# MCU.net
KiCad netlist of a schematic drawn in Altium Designer
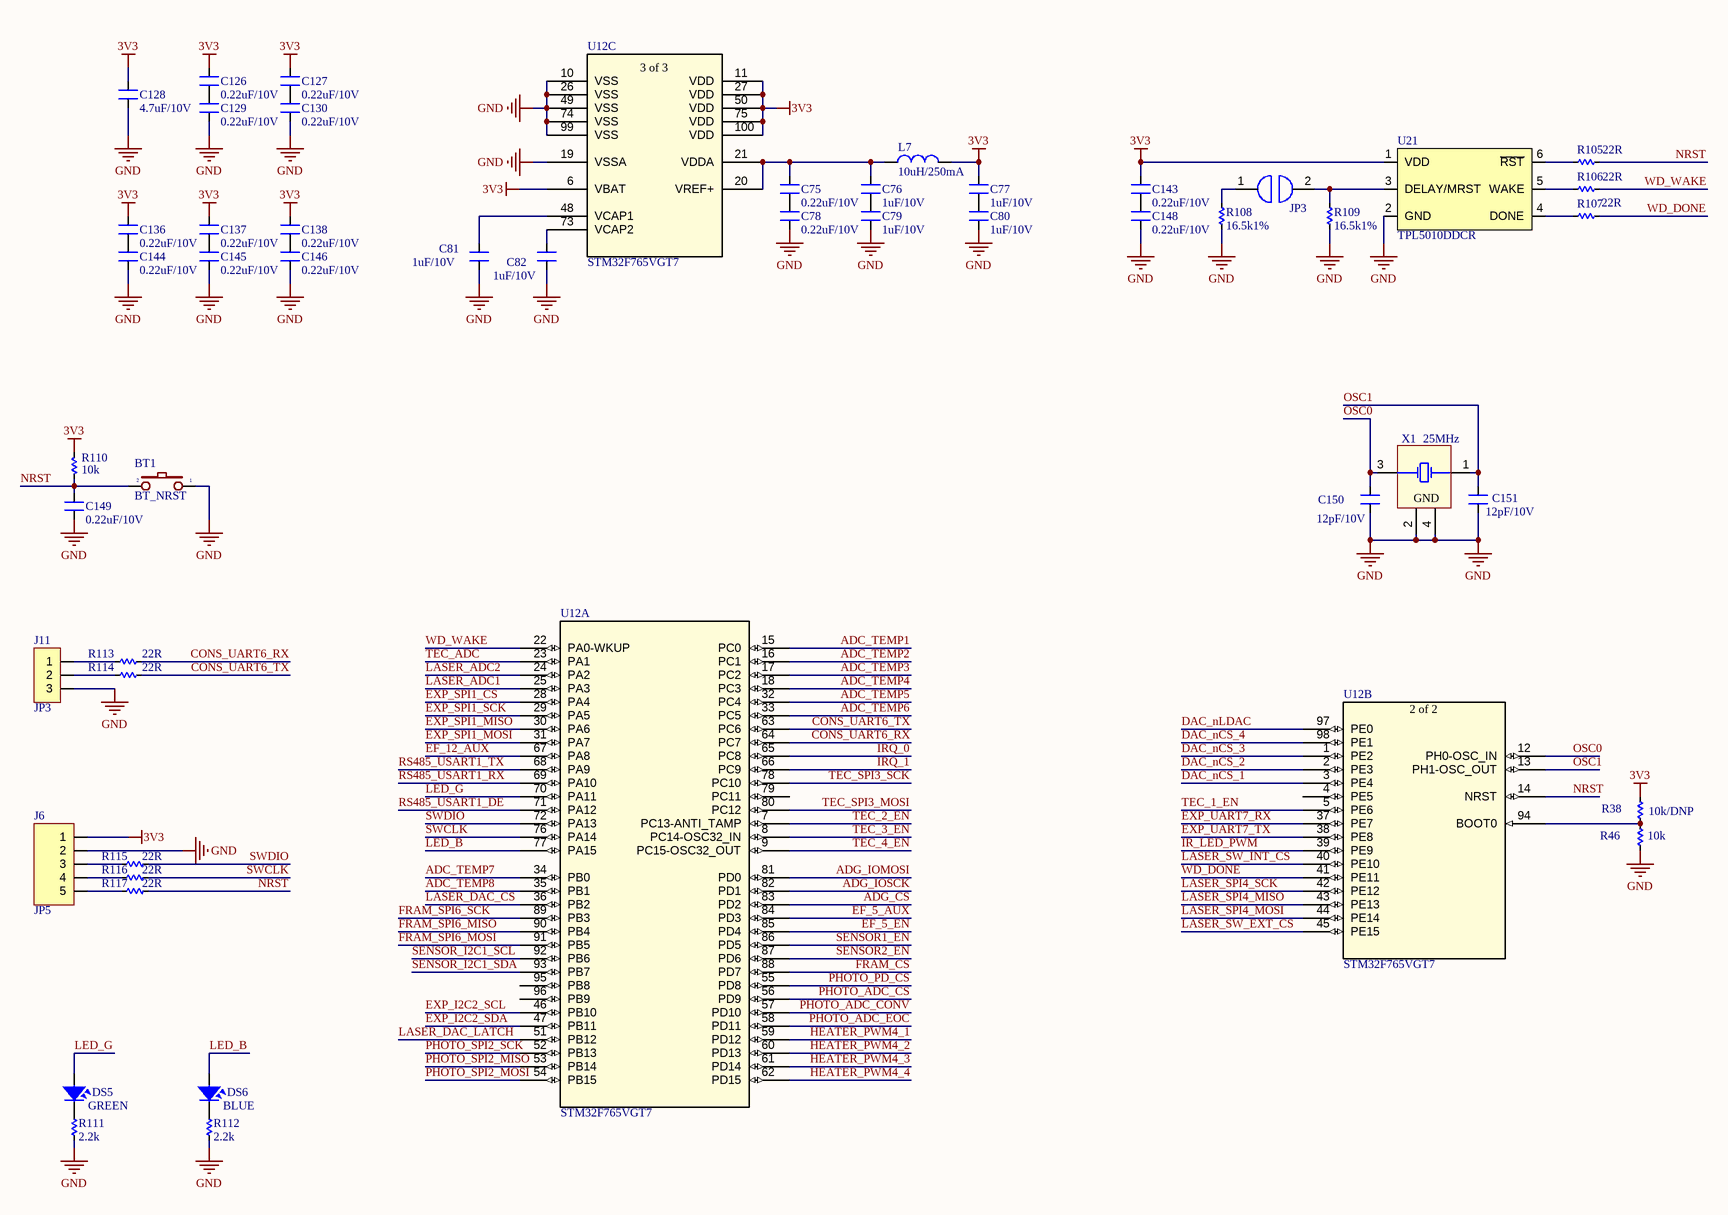
[diagram p0: MCU.SchDoc]

(export (version "E")
  (design (tool "Eeschema 10.0.6"))
  (components
    (comp (ref "BT1")
      (value "BT_NRST")
      (footprint "SW1-SMD")
      (description "Switch button 2 pin")
      (libsource (lib "EXP_HW_V3") (part "SW2"))
    )
    (comp (ref "C75")
      (value "0.22uF/10V")
      (footprint "CAP_C_1608X80")
      (libsource (lib "EXP_HW_V3") (part "Capacitors"))
    )
    (comp (ref "C76")
      (value "1uF/10V")
      (footprint "CAP_C_1608X80")
      (libsource (lib "EXP_HW_V3") (part "Capacitors"))
    )
    (comp (ref "C77")
      (value "1uF/10V")
      (footprint "CAP_C_1608X80")
      (libsource (lib "EXP_HW_V3") (part "Capacitors"))
    )
    (comp (ref "C78")
      (value "0.22uF/10V")
      (footprint "CAP_C_1608X80")
      (libsource (lib "EXP_HW_V3") (part "Capacitors"))
    )
    (comp (ref "C79")
      (value "1uF/10V")
      (footprint "CAP_C_1608X80")
      (libsource (lib "EXP_HW_V3") (part "Capacitors"))
    )
    (comp (ref "C80")
      (value "1uF/10V")
      (footprint "CAP_C_1608X80")
      (libsource (lib "EXP_HW_V3") (part "Capacitors"))
    )
    (comp (ref "C81")
      (value "1uF/10V")
      (footprint "CAP_C_1608X80")
      (libsource (lib "EXP_HW_V3") (part "Capacitors"))
    )
    (comp (ref "C82")
      (value "1uF/10V")
      (footprint "CAP_C_1608X80")
      (libsource (lib "EXP_HW_V3") (part "Capacitors"))
    )
    (comp (ref "C126")
      (value "0.22uF/10V")
      (footprint "CAP_C_1608X80")
      (libsource (lib "EXP_HW_V3") (part "Capacitors"))
    )
    (comp (ref "C127")
      (value "0.22uF/10V")
      (footprint "CAP_C_1608X80")
      (libsource (lib "EXP_HW_V3") (part "Capacitors"))
    )
    (comp (ref "C128")
      (value "4.7uF/10V")
      (footprint "CAP_C_1608X80")
      (libsource (lib "EXP_HW_V3") (part "Capacitors"))
    )
    (comp (ref "C129")
      (value "0.22uF/10V")
      (footprint "CAP_C_1608X80")
      (libsource (lib "EXP_HW_V3") (part "Capacitors"))
    )
    (comp (ref "C130")
      (value "0.22uF/10V")
      (footprint "CAP_C_1608X80")
      (libsource (lib "EXP_HW_V3") (part "Capacitors"))
    )
    (comp (ref "C136")
      (value "0.22uF/10V")
      (footprint "CAP_C_1608X80")
      (libsource (lib "EXP_HW_V3") (part "Capacitors"))
    )
    (comp (ref "C137")
      (value "0.22uF/10V")
      (footprint "CAP_C_1608X80")
      (libsource (lib "EXP_HW_V3") (part "Capacitors"))
    )
    (comp (ref "C138")
      (value "0.22uF/10V")
      (footprint "CAP_C_1608X80")
      (libsource (lib "EXP_HW_V3") (part "Capacitors"))
    )
    (comp (ref "C143")
      (value "0.22uF/10V")
      (footprint "CAP_C_1608X80")
      (libsource (lib "EXP_HW_V3") (part "Capacitors"))
    )
    (comp (ref "C144")
      (value "0.22uF/10V")
      (footprint "CAP_C_1608X80")
      (libsource (lib "EXP_HW_V3") (part "Capacitors"))
    )
    (comp (ref "C145")
      (value "0.22uF/10V")
      (footprint "CAP_C_1608X80")
      (libsource (lib "EXP_HW_V3") (part "Capacitors"))
    )
    (comp (ref "C146")
      (value "0.22uF/10V")
      (footprint "CAP_C_1608X80")
      (libsource (lib "EXP_HW_V3") (part "Capacitors"))
    )
    (comp (ref "C148")
      (value "0.22uF/10V")
      (footprint "CAP_C_1608X80")
      (libsource (lib "EXP_HW_V3") (part "Capacitors"))
    )
    (comp (ref "C149")
      (value "0.22uF/10V")
      (footprint "CAP_C_1608X80")
      (libsource (lib "EXP_HW_V3") (part "Capacitors"))
    )
    (comp (ref "C150")
      (value "12pF/10V")
      (footprint "CAP_C_1608X80")
      (libsource (lib "EXP_HW_V3") (part "Capacitors"))
    )
    (comp (ref "C151")
      (value "12pF/10V")
      (footprint "CAP_C_1608X80")
      (libsource (lib "EXP_HW_V3") (part "Capacitors"))
    )
    (comp (ref "DS5")
      (value "GREEN")
      (footprint "LED-0603-BLUE")
      (libsource (lib "EXP_HW_V3") (part "LED SMD"))
    )
    (comp (ref "DS6")
      (value "BLUE")
      (footprint "LED-0603-BLUE")
      (libsource (lib "EXP_HW_V3") (part "LED SMD"))
    )
    (comp (ref "J6")
      (value "JP5")
      (footprint "JP5-D1C")
      (description "WR-PHD 2.54 mm Angled Socket Header")
      (fields
        (field (name "MANUFACTURER") "Würth Elektronik eiSos GmbH")
        (field (name "PARTNO") "613005143121")
        (field (name "CREATED BY") "Karrer Zheng")
      )
      (libsource (lib "EXP_HW_V3") (part "JP5"))
    )
    (comp (ref "J11")
      (value "JP3")
      (footprint "JP3-D1C")
      (description "WR-PHD 2.54 mm Angled Socket Header")
      (fields
        (field (name "MANUFACTURER") "Würth Elektronik eiSos GmbH")
        (field (name "PARTNO") "613003143121")
        (field (name "CREATED BY") "Karrer Zheng")
      )
      (libsource (lib "EXP_HW_V3") (part "JP3"))
    )
    (comp (ref "JP3") (value "jumper2") (footprint "JUMPER2") (libsource (lib "EXP_HW_V3") (part "JUMPER")))
    (comp (ref "L7")
      (value "10uH/250mA")
      (footprint "L-SMD-0603")
      (fields
        (field (name "PARTNO") "78477010")
        (field (name "MANUFACTURER") "Wurth Elektronik")
        (field (name "CREATED BY") "Baojun Chen")
      )
      (libsource (lib "EXP_HW_V3") (part "L-SMD-1"))
    )
    (comp (ref "R38")
      (value "10k/DNP")
      (footprint "RES_C_1608X60")
      (description "SMD")
      (fields
        (field (name "MANUFACTURER") "Generic Components")
        (field (name "PUBLISHER") "Altium Hobart Technology Centre")
      )
      (libsource (lib "EXP_HW_V3") (part "Res SMD"))
    )
    (comp (ref "R46")
      (value "10k")
      (footprint "RES_C_1608X60")
      (description "SMD")
      (fields
        (field (name "MANUFACTURER") "Generic Components")
        (field (name "PUBLISHER") "Altium Hobart Technology Centre")
      )
      (libsource (lib "EXP_HW_V3") (part "Res SMD"))
    )
    (comp (ref "R105")
      (value "22R")
      (footprint "RES_C_1608X60")
      (description "SMD")
      (fields
        (field (name "MANUFACTURER") "Generic Components")
        (field (name "PUBLISHER") "Altium Hobart Technology Centre")
      )
      (libsource (lib "EXP_HW_V3") (part "Res SMD"))
    )
    (comp (ref "R106")
      (value "22R")
      (footprint "RES_C_1608X60")
      (description "SMD")
      (fields
        (field (name "MANUFACTURER") "Generic Components")
        (field (name "PUBLISHER") "Altium Hobart Technology Centre")
      )
      (libsource (lib "EXP_HW_V3") (part "Res SMD"))
    )
    (comp (ref "R107")
      (value "22R")
      (footprint "RES_C_1608X60")
      (description "SMD")
      (fields
        (field (name "MANUFACTURER") "Generic Components")
        (field (name "PUBLISHER") "Altium Hobart Technology Centre")
      )
      (libsource (lib "EXP_HW_V3") (part "Res SMD"))
    )
    (comp (ref "R108")
      (value "16.5k1%")
      (footprint "RES_C_1608X60")
      (description "SMD")
      (fields
        (field (name "MANUFACTURER") "Generic Components")
        (field (name "PUBLISHER") "Altium Hobart Technology Centre")
      )
      (libsource (lib "EXP_HW_V3") (part "Res SMD"))
    )
    (comp (ref "R109")
      (value "16.5k1%")
      (footprint "RES_C_1608X60")
      (description "SMD")
      (fields
        (field (name "MANUFACTURER") "Generic Components")
        (field (name "PUBLISHER") "Altium Hobart Technology Centre")
      )
      (libsource (lib "EXP_HW_V3") (part "Res SMD"))
    )
    (comp (ref "R110")
      (value "10k")
      (footprint "RES_C_1608X60")
      (description "SMD")
      (fields
        (field (name "MANUFACTURER") "Generic Components")
        (field (name "PUBLISHER") "Altium Hobart Technology Centre")
      )
      (libsource (lib "EXP_HW_V3") (part "Res SMD"))
    )
    (comp (ref "R111")
      (value "2.2k")
      (footprint "RES_C_1608X60")
      (description "SMD")
      (fields
        (field (name "MANUFACTURER") "Generic Components")
        (field (name "PUBLISHER") "Altium Hobart Technology Centre")
      )
      (libsource (lib "EXP_HW_V3") (part "Res SMD"))
    )
    (comp (ref "R112")
      (value "2.2k")
      (footprint "RES_C_1608X60")
      (description "SMD")
      (fields
        (field (name "MANUFACTURER") "Generic Components")
        (field (name "PUBLISHER") "Altium Hobart Technology Centre")
      )
      (libsource (lib "EXP_HW_V3") (part "Res SMD"))
    )
    (comp (ref "R113")
      (value "22R")
      (footprint "RES_C_1608X60")
      (description "SMD")
      (fields
        (field (name "MANUFACTURER") "Generic Components")
        (field (name "PUBLISHER") "Altium Hobart Technology Centre")
      )
      (libsource (lib "EXP_HW_V3") (part "Res SMD"))
    )
    (comp (ref "R114")
      (value "22R")
      (footprint "RES_C_1608X60")
      (description "SMD")
      (fields
        (field (name "MANUFACTURER") "Generic Components")
        (field (name "PUBLISHER") "Altium Hobart Technology Centre")
      )
      (libsource (lib "EXP_HW_V3") (part "Res SMD"))
    )
    (comp (ref "R115")
      (value "22R")
      (footprint "RES_C_1608X60")
      (description "SMD")
      (fields
        (field (name "MANUFACTURER") "Generic Components")
        (field (name "PUBLISHER") "Altium Hobart Technology Centre")
      )
      (libsource (lib "EXP_HW_V3") (part "Res SMD"))
    )
    (comp (ref "R116")
      (value "22R")
      (footprint "RES_C_1608X60")
      (description "SMD")
      (fields
        (field (name "MANUFACTURER") "Generic Components")
        (field (name "PUBLISHER") "Altium Hobart Technology Centre")
      )
      (libsource (lib "EXP_HW_V3") (part "Res SMD"))
    )
    (comp (ref "R117")
      (value "22R")
      (footprint "RES_C_1608X60")
      (description "SMD")
      (fields
        (field (name "MANUFACTURER") "Generic Components")
        (field (name "PUBLISHER") "Altium Hobart Technology Centre")
      )
      (libsource (lib "EXP_HW_V3") (part "Res SMD"))
    )
    (comp (ref "U12")
      (value "STM32F765VGT7")
      (footprint "LQFP100_STM")
      (description "No Description Available")
      (libsource (lib "EXP_HW_V3") (part "STM32F765VGT7"))
    )
    (comp (ref "U21")
      (value "TPL5010DDCR")
      (footprint "TPL5010DDCR")
      (description "IC OSC PROG TIMER TSOT23-6")
      (libsource (lib "EXP_HW_V3") (part "TPL5010DDCR"))
    )
    (comp (ref "X1")
      (value "25MHz")
      (footprint "XTAL_ECS-250-12-33Q-JES-TR")
      (description "Crystal, 8 MHz, -30 to 85 degC, 3.2 x 2.5 x 0.9 mm SMD")
      (libsource (lib "Library") (part "XT4"))
    )
  )
  (nets
    (net (code "1") (name "/ADC_TEMP1") (class "Default")
      (node (ref "U12") (pin "15") (pinfunction "PC0_15") (pintype "bidirectional"))
    )
    (net (code "2") (name "/ADC_TEMP2") (class "Default")
      (node (ref "U12") (pin "16") (pinfunction "PC1_16") (pintype "bidirectional"))
    )
    (net (code "3") (name "/ADC_TEMP3") (class "Default")
      (node (ref "U12") (pin "17") (pinfunction "PC2_17") (pintype "bidirectional"))
    )
    (net (code "4") (name "/ADC_TEMP4") (class "Default")
      (node (ref "U12") (pin "18") (pinfunction "PC3_18") (pintype "bidirectional"))
    )
    (net (code "5") (name "/ADC_TEMP5") (class "Default")
      (node (ref "U12") (pin "32") (pinfunction "PC4_32") (pintype "bidirectional"))
    )
    (net (code "6") (name "/ADC_TEMP6") (class "Default")
      (node (ref "U12") (pin "33") (pinfunction "PC5_33") (pintype "bidirectional"))
    )
    (net (code "7") (name "/ADC_TEMP7") (class "Default")
      (node (ref "U12") (pin "34") (pinfunction "PB0_34") (pintype "bidirectional"))
    )
    (net (code "8") (name "/ADC_TEMP8") (class "Default")
      (node (ref "U12") (pin "35") (pinfunction "PB1_35") (pintype "bidirectional"))
    )
    (net (code "9") (name "/ADG_CS") (class "Default")
      (node (ref "U12") (pin "83") (pinfunction "PD2_83") (pintype "bidirectional"))
    )
    (net (code "10") (name "/ADG_IOMOSI") (class "Default")
      (node (ref "U12") (pin "81") (pinfunction "PD0_81") (pintype "bidirectional"))
    )
    (net (code "11") (name "/ADG_IOSCK") (class "Default")
      (node (ref "U12") (pin "82") (pinfunction "PD1_82") (pintype "bidirectional"))
    )
    (net (code "12") (name "/CONS_UART6_RX") (class "Default")
      (node (ref "R113") (pin "1") (pinfunction "1_1") (pintype "passive"))
      (node (ref "U12") (pin "64") (pinfunction "PC7_64") (pintype "bidirectional"))
    )
    (net (code "13") (name "/CONS_UART6_TX") (class "Default")
      (node (ref "R114") (pin "1") (pinfunction "1_1") (pintype "passive"))
      (node (ref "U12") (pin "63") (pinfunction "PC6_63") (pintype "bidirectional"))
    )
    (net (code "14") (name "/DAC_nCS_1") (class "Default")
      (node (ref "U12") (pin "3") (pinfunction "PE4_3") (pintype "bidirectional"))
    )
    (net (code "15") (name "/DAC_nCS_2") (class "Default")
      (node (ref "U12") (pin "2") (pinfunction "PE3_2") (pintype "bidirectional"))
    )
    (net (code "16") (name "/DAC_nCS_3") (class "Default")
      (node (ref "U12") (pin "1") (pinfunction "PE2_1") (pintype "bidirectional"))
    )
    (net (code "17") (name "/DAC_nCS_4") (class "Default")
      (node (ref "U12") (pin "98") (pinfunction "PE1_98") (pintype "bidirectional"))
    )
    (net (code "18") (name "/DAC_nLDAC") (class "Default")
      (node (ref "U12") (pin "97") (pinfunction "PE0_97") (pintype "bidirectional"))
    )
    (net (code "19") (name "/EF_5_AUX") (class "Default")
      (node (ref "U12") (pin "84") (pinfunction "PD3_84") (pintype "bidirectional"))
    )
    (net (code "20") (name "/EF_5_EN") (class "Default")
      (node (ref "U12") (pin "85") (pinfunction "PD4_85") (pintype "bidirectional"))
    )
    (net (code "21") (name "/EF_12_AUX") (class "Default")
      (node (ref "U12") (pin "67") (pinfunction "PA8_67") (pintype "bidirectional"))
    )
    (net (code "22") (name "/EXP_I2C2_SCL") (class "Default")
      (node (ref "U12") (pin "46") (pinfunction "PB10_46") (pintype "bidirectional"))
    )
    (net (code "23") (name "/EXP_I2C2_SDA") (class "Default")
      (node (ref "U12") (pin "47") (pinfunction "PB11_47") (pintype "bidirectional"))
    )
    (net (code "24") (name "/EXP_SPI1_CS") (class "Default")
      (node (ref "U12") (pin "28") (pinfunction "PA4_28") (pintype "bidirectional"))
    )
    (net (code "25") (name "/EXP_SPI1_MISO") (class "Default")
      (node (ref "U12") (pin "30") (pinfunction "PA6_30") (pintype "bidirectional"))
    )
    (net (code "26") (name "/EXP_SPI1_MOSI") (class "Default")
      (node (ref "U12") (pin "31") (pinfunction "PA7_31") (pintype "bidirectional"))
    )
    (net (code "27") (name "/EXP_SPI1_SCK") (class "Default")
      (node (ref "U12") (pin "29") (pinfunction "PA5_29") (pintype "bidirectional"))
    )
    (net (code "28") (name "/EXP_UART7_RX") (class "Default")
      (node (ref "U12") (pin "37") (pinfunction "PE7_37") (pintype "bidirectional"))
    )
    (net (code "29") (name "/EXP_UART7_TX") (class "Default")
      (node (ref "U12") (pin "38") (pinfunction "PE8_38") (pintype "bidirectional"))
    )
    (net (code "30") (name "/FRAM_CS") (class "Default")
      (node (ref "U12") (pin "88") (pinfunction "PD7_88") (pintype "bidirectional"))
    )
    (net (code "31") (name "/FRAM_SPI6_MISO") (class "Default")
      (node (ref "U12") (pin "90") (pinfunction "PB4_90") (pintype "bidirectional"))
    )
    (net (code "32") (name "/FRAM_SPI6_MOSI") (class "Default")
      (node (ref "U12") (pin "91") (pinfunction "PB5_91") (pintype "bidirectional"))
    )
    (net (code "33") (name "/FRAM_SPI6_SCK") (class "Default")
      (node (ref "U12") (pin "89") (pinfunction "PB3_89") (pintype "bidirectional"))
    )
    (net (code "34") (name "/HEATER_PWM4_1") (class "Default")
      (node (ref "U12") (pin "59") (pinfunction "PD12_59") (pintype "bidirectional"))
    )
    (net (code "35") (name "/HEATER_PWM4_2") (class "Default")
      (node (ref "U12") (pin "60") (pinfunction "PD13_60") (pintype "bidirectional"))
    )
    (net (code "36") (name "/HEATER_PWM4_3") (class "Default")
      (node (ref "U12") (pin "61") (pinfunction "PD14_61") (pintype "bidirectional"))
    )
    (net (code "37") (name "/HEATER_PWM4_4") (class "Default")
      (node (ref "U12") (pin "62") (pinfunction "PD15_62") (pintype "bidirectional"))
    )
    (net (code "38") (name "/IRQ_0") (class "Default")
      (node (ref "U12") (pin "65") (pinfunction "PC8_65") (pintype "bidirectional"))
    )
    (net (code "39") (name "/IRQ_1") (class "Default")
      (node (ref "U12") (pin "66") (pinfunction "PC9_66") (pintype "bidirectional"))
    )
    (net (code "40") (name "/IR_LED_PWM") (class "Default")
      (node (ref "U12") (pin "39") (pinfunction "PE9_39") (pintype "bidirectional"))
    )
    (net (code "41") (name "/LASER_ADC1") (class "Default")
      (node (ref "U12") (pin "25") (pinfunction "PA3_25") (pintype "bidirectional"))
    )
    (net (code "42") (name "/LASER_ADC2") (class "Default")
      (node (ref "U12") (pin "24") (pinfunction "PA2_24") (pintype "bidirectional"))
    )
    (net (code "43") (name "/LASER_DAC_CS") (class "Default")
      (node (ref "U12") (pin "36") (pinfunction "PB2_36") (pintype "bidirectional"))
    )
    (net (code "44") (name "/LASER_DAC_LATCH") (class "Default")
      (node (ref "U12") (pin "51") (pinfunction "PB12_51") (pintype "bidirectional"))
    )
    (net (code "45") (name "/LASER_SPI4_MISO") (class "Default")
      (node (ref "U12") (pin "43") (pinfunction "PE13_43") (pintype "bidirectional"))
    )
    (net (code "46") (name "/LASER_SPI4_MOSI") (class "Default")
      (node (ref "U12") (pin "44") (pinfunction "PE14_44") (pintype "bidirectional"))
    )
    (net (code "47") (name "/LASER_SPI4_SCK") (class "Default")
      (node (ref "U12") (pin "42") (pinfunction "PE12_42") (pintype "bidirectional"))
    )
    (net (code "48") (name "/LASER_SW_EXT_CS") (class "Default")
      (node (ref "U12") (pin "45") (pinfunction "PE15_45") (pintype "bidirectional"))
    )
    (net (code "49") (name "/LASER_SW_INT_CS") (class "Default")
      (node (ref "U12") (pin "40") (pinfunction "PE10_40") (pintype "bidirectional"))
    )
    (net (code "50") (name "/LED_B") (class "Default")
      (node (ref "DS6") (pin "1") (pinfunction "1_1") (pintype "passive"))
      (node (ref "U12") (pin "77") (pinfunction "PA15_77") (pintype "bidirectional"))
    )
    (net (code "51") (name "/LED_G") (class "Default")
      (node (ref "DS5") (pin "1") (pinfunction "1_1") (pintype "passive"))
      (node (ref "U12") (pin "70") (pinfunction "PA11_70") (pintype "bidirectional"))
    )
    (net (code "52") (name "/NRST") (class "Default")
      (node (ref "BT1") (pin "2") (pinfunction "2_2") (pintype "passive"))
      (node (ref "C149") (pin "2") (pinfunction "2_2") (pintype "passive"))
      (node (ref "R105") (pin "2") (pinfunction "2_2") (pintype "passive"))
      (node (ref "R110") (pin "2") (pinfunction "2_2") (pintype "passive"))
      (node (ref "R117") (pin "1") (pinfunction "1_1") (pintype "passive"))
      (node (ref "U12") (pin "14") (pinfunction "NRST_14") (pintype "bidirectional"))
    )
    (net (code "53") (name "/OSC0") (class "Default")
      (node (ref "C150") (pin "1") (pinfunction "1_1") (pintype "passive"))
      (node (ref "U12") (pin "12") (pinfunction "PH0-OSC_IN_12") (pintype "bidirectional"))
      (node (ref "X1") (pin "3") (pinfunction "XTAL_3") (pintype "passive"))
    )
    (net (code "54") (name "/OSC1") (class "Default")
      (node (ref "C151") (pin "2") (pinfunction "2_2") (pintype "passive"))
      (node (ref "U12") (pin "13") (pinfunction "PH1-OSC_OUT_13") (pintype "bidirectional"))
      (node (ref "X1") (pin "1") (pinfunction "XTAL_1") (pintype "passive"))
    )
    (net (code "55") (name "/PHOTO_ADC_CONV") (class "Default")
      (node (ref "U12") (pin "57") (pinfunction "PD10_57") (pintype "bidirectional"))
    )
    (net (code "56") (name "/PHOTO_ADC_CS") (class "Default")
      (node (ref "U12") (pin "56") (pinfunction "PD9_56") (pintype "bidirectional"))
    )
    (net (code "57") (name "/PHOTO_ADC_EOC") (class "Default")
      (node (ref "U12") (pin "58") (pinfunction "PD11_58") (pintype "bidirectional"))
    )
    (net (code "58") (name "/PHOTO_PD_CS") (class "Default")
      (node (ref "U12") (pin "55") (pinfunction "PD8_55") (pintype "bidirectional"))
    )
    (net (code "59") (name "/PHOTO_SPI2_MISO") (class "Default")
      (node (ref "U12") (pin "53") (pinfunction "PB14_53") (pintype "bidirectional"))
    )
    (net (code "60") (name "/PHOTO_SPI2_MOSI") (class "Default")
      (node (ref "U12") (pin "54") (pinfunction "PB15_54") (pintype "bidirectional"))
    )
    (net (code "61") (name "/PHOTO_SPI2_SCK") (class "Default")
      (node (ref "U12") (pin "52") (pinfunction "PB13_52") (pintype "bidirectional"))
    )
    (net (code "62") (name "/RS485_USART1_DE") (class "Default")
      (node (ref "U12") (pin "71") (pinfunction "PA12_71") (pintype "bidirectional"))
    )
    (net (code "63") (name "/RS485_USART1_RX") (class "Default")
      (node (ref "U12") (pin "69") (pinfunction "PA10_69") (pintype "bidirectional"))
    )
    (net (code "64") (name "/RS485_USART1_TX") (class "Default")
      (node (ref "U12") (pin "68") (pinfunction "PA9_68") (pintype "bidirectional"))
    )
    (net (code "65") (name "/SENSOR1_EN") (class "Default")
      (node (ref "U12") (pin "86") (pinfunction "PD5_86") (pintype "bidirectional"))
    )
    (net (code "66") (name "/SENSOR2_EN") (class "Default")
      (node (ref "U12") (pin "87") (pinfunction "PD6_87") (pintype "bidirectional"))
    )
    (net (code "67") (name "/SENSOR_I2C1_SCL") (class "Default")
      (node (ref "U12") (pin "92") (pinfunction "PB6_92") (pintype "bidirectional"))
    )
    (net (code "68") (name "/SENSOR_I2C1_SDA") (class "Default")
      (node (ref "U12") (pin "93") (pinfunction "PB7_93") (pintype "bidirectional"))
    )
    (net (code "69") (name "/SWCLK") (class "Default")
      (node (ref "R116") (pin "1") (pinfunction "1_1") (pintype "passive"))
      (node (ref "U12") (pin "76") (pinfunction "PA14_76") (pintype "bidirectional"))
    )
    (net (code "70") (name "/SWDIO") (class "Default")
      (node (ref "R115") (pin "1") (pinfunction "1_1") (pintype "passive"))
      (node (ref "U12") (pin "72") (pinfunction "PA13_72") (pintype "bidirectional"))
    )
    (net (code "71") (name "/TEC_1_EN") (class "Default")
      (node (ref "U12") (pin "5") (pinfunction "PE6_5") (pintype "bidirectional"))
    )
    (net (code "72") (name "/TEC_2_EN") (class "Default")
      (node (ref "U12") (pin "7") (pinfunction "PC13-ANTI_TAMP_7") (pintype "bidirectional"))
    )
    (net (code "73") (name "/TEC_3_EN") (class "Default")
      (node (ref "U12") (pin "8") (pinfunction "PC14-OSC32_IN_8") (pintype "bidirectional"))
    )
    (net (code "74") (name "/TEC_4_EN") (class "Default")
      (node (ref "U12") (pin "9") (pinfunction "PC15-OSC32_OUT_9") (pintype "bidirectional"))
    )
    (net (code "75") (name "/TEC_ADC") (class "Default")
      (node (ref "U12") (pin "23") (pinfunction "PA1_23") (pintype "bidirectional"))
    )
    (net (code "76") (name "/TEC_SPI3_MOSI") (class "Default")
      (node (ref "U12") (pin "80") (pinfunction "PC12_80") (pintype "bidirectional"))
    )
    (net (code "77") (name "/TEC_SPI3_SCK") (class "Default")
      (node (ref "U12") (pin "78") (pinfunction "PC10_78") (pintype "bidirectional"))
    )
    (net (code "78") (name "/WD_DONE") (class "Default")
      (node (ref "R107") (pin "2") (pinfunction "2_2") (pintype "passive"))
      (node (ref "U12") (pin "41") (pinfunction "PE11_41") (pintype "bidirectional"))
    )
    (net (code "79") (name "/WD_WAKE") (class "Default")
      (node (ref "R106") (pin "2") (pinfunction "2_2") (pintype "passive"))
      (node (ref "U12") (pin "22") (pinfunction "PA0-WKUP_22") (pintype "bidirectional"))
    )
    (net (code "80") (name "3V3") (class "Default")
      (node (ref "C126") (pin "2") (pinfunction "2_2") (pintype "passive"))
      (node (ref "C127") (pin "2") (pinfunction "2_2") (pintype "passive"))
      (node (ref "C128") (pin "2") (pinfunction "2_2") (pintype "passive"))
      (node (ref "C136") (pin "2") (pinfunction "2_2") (pintype "passive"))
      (node (ref "C137") (pin "2") (pinfunction "2_2") (pintype "passive"))
      (node (ref "C138") (pin "2") (pinfunction "2_2") (pintype "passive"))
      (node (ref "C143") (pin "2") (pinfunction "2_2") (pintype "passive"))
      (node (ref "C77") (pin "2") (pinfunction "2_2") (pintype "passive"))
      (node (ref "J6") (pin "1") (pinfunction "1_1") (pintype "passive"))
      (node (ref "L7") (pin "1") (pinfunction "1_1") (pintype "passive"))
      (node (ref "R110") (pin "1") (pinfunction "1_1") (pintype "passive"))
      (node (ref "R38") (pin "1") (pinfunction "1_1") (pintype "passive"))
      (node (ref "U12") (pin "100") (pinfunction "VDD_100") (pintype "power_in"))
      (node (ref "U12") (pin "11") (pinfunction "VDD_11") (pintype "power_in"))
      (node (ref "U12") (pin "27") (pinfunction "VDD_27") (pintype "power_in"))
      (node (ref "U12") (pin "50") (pinfunction "VDD_50") (pintype "power_in"))
      (node (ref "U12") (pin "6") (pinfunction "VBAT_6") (pintype "power_in"))
      (node (ref "U12") (pin "75") (pinfunction "VDD_75") (pintype "power_in"))
      (node (ref "U21") (pin "1") (pinfunction "VDD_1") (pintype "passive"))
    )
    (net (code "81") (name "GND") (class "Default")
      (node (ref "BT1") (pin "1") (pinfunction "1_1") (pintype "passive"))
      (node (ref "C128") (pin "1") (pinfunction "1_1") (pintype "passive"))
      (node (ref "C129") (pin "1") (pinfunction "1_1") (pintype "passive"))
      (node (ref "C130") (pin "1") (pinfunction "1_1") (pintype "passive"))
      (node (ref "C144") (pin "1") (pinfunction "1_1") (pintype "passive"))
      (node (ref "C145") (pin "1") (pinfunction "1_1") (pintype "passive"))
      (node (ref "C146") (pin "1") (pinfunction "1_1") (pintype "passive"))
      (node (ref "C148") (pin "1") (pinfunction "1_1") (pintype "passive"))
      (node (ref "C149") (pin "1") (pinfunction "1_1") (pintype "passive"))
      (node (ref "C150") (pin "2") (pinfunction "2_2") (pintype "passive"))
      (node (ref "C151") (pin "1") (pinfunction "1_1") (pintype "passive"))
      (node (ref "C78") (pin "1") (pinfunction "1_1") (pintype "passive"))
      (node (ref "C79") (pin "1") (pinfunction "1_1") (pintype "passive"))
      (node (ref "C80") (pin "1") (pinfunction "1_1") (pintype "passive"))
      (node (ref "C81") (pin "1") (pinfunction "1_1") (pintype "passive"))
      (node (ref "C82") (pin "1") (pinfunction "1_1") (pintype "passive"))
      (node (ref "J11") (pin "3") (pinfunction "3_3") (pintype "passive"))
      (node (ref "J6") (pin "2") (pinfunction "2_2") (pintype "passive"))
      (node (ref "R108") (pin "1") (pinfunction "1_1") (pintype "passive"))
      (node (ref "R109") (pin "1") (pinfunction "1_1") (pintype "passive"))
      (node (ref "R111") (pin "2") (pinfunction "2_2") (pintype "passive"))
      (node (ref "R112") (pin "2") (pinfunction "2_2") (pintype "passive"))
      (node (ref "R46") (pin "2") (pinfunction "2_2") (pintype "passive"))
      (node (ref "U12") (pin "10") (pinfunction "VSS_10") (pintype "power_in"))
      (node (ref "U12") (pin "19") (pinfunction "VSSA_19") (pintype "power_in"))
      (node (ref "U12") (pin "26") (pinfunction "VSS_26") (pintype "power_in"))
      (node (ref "U12") (pin "49") (pinfunction "VSS_49") (pintype "power_in"))
      (node (ref "U12") (pin "74") (pinfunction "VSS_74") (pintype "power_in"))
      (node (ref "U12") (pin "99") (pinfunction "VSS_99") (pintype "power_in"))
      (node (ref "U21") (pin "2") (pinfunction "GND_2") (pintype "passive"))
      (node (ref "X1") (pin "2") (pinfunction "GND_2") (pintype "power_in"))
      (node (ref "X1") (pin "4") (pinfunction "GND_4") (pintype "power_in"))
    )
    (net (code "82") (name "Net-(C75-Pad1)") (class "Default")
      (node (ref "C75") (pin "1") (pinfunction "1_1") (pintype "passive"))
      (node (ref "C78") (pin "2") (pinfunction "2_2") (pintype "passive"))
    )
    (net (code "83") (name "Net-(C76-Pad1)") (class "Default")
      (node (ref "C76") (pin "1") (pinfunction "1_1") (pintype "passive"))
      (node (ref "C79") (pin "2") (pinfunction "2_2") (pintype "passive"))
    )
    (net (code "84") (name "Net-(C77-Pad1)") (class "Default")
      (node (ref "C77") (pin "1") (pinfunction "1_1") (pintype "passive"))
      (node (ref "C80") (pin "2") (pinfunction "2_2") (pintype "passive"))
    )
    (net (code "85") (name "Net-(C126-Pad1)") (class "Default")
      (node (ref "C126") (pin "1") (pinfunction "1_1") (pintype "passive"))
      (node (ref "C129") (pin "2") (pinfunction "2_2") (pintype "passive"))
    )
    (net (code "86") (name "Net-(C127-Pad1)") (class "Default")
      (node (ref "C127") (pin "1") (pinfunction "1_1") (pintype "passive"))
      (node (ref "C130") (pin "2") (pinfunction "2_2") (pintype "passive"))
    )
    (net (code "87") (name "Net-(C136-Pad1)") (class "Default")
      (node (ref "C136") (pin "1") (pinfunction "1_1") (pintype "passive"))
      (node (ref "C144") (pin "2") (pinfunction "2_2") (pintype "passive"))
    )
    (net (code "88") (name "Net-(C137-Pad1)") (class "Default")
      (node (ref "C137") (pin "1") (pinfunction "1_1") (pintype "passive"))
      (node (ref "C145") (pin "2") (pinfunction "2_2") (pintype "passive"))
    )
    (net (code "89") (name "Net-(C138-Pad1)") (class "Default")
      (node (ref "C138") (pin "1") (pinfunction "1_1") (pintype "passive"))
      (node (ref "C146") (pin "2") (pinfunction "2_2") (pintype "passive"))
    )
    (net (code "90") (name "Net-(C143-Pad1)") (class "Default")
      (node (ref "C143") (pin "1") (pinfunction "1_1") (pintype "passive"))
      (node (ref "C148") (pin "2") (pinfunction "2_2") (pintype "passive"))
    )
    (net (code "91") (name "Net-(DS5-Pad2)") (class "Default")
      (node (ref "DS5") (pin "2") (pinfunction "2_2") (pintype "passive"))
      (node (ref "R111") (pin "1") (pinfunction "1_1") (pintype "passive"))
    )
    (net (code "92") (name "Net-(DS6-Pad2)") (class "Default")
      (node (ref "DS6") (pin "2") (pinfunction "2_2") (pintype "passive"))
      (node (ref "R112") (pin "1") (pinfunction "1_1") (pintype "passive"))
    )
    (net (code "93") (name "Net-(J6-Pad3)") (class "Default")
      (node (ref "J6") (pin "3") (pinfunction "3_3") (pintype "passive"))
      (node (ref "R115") (pin "2") (pinfunction "2_2") (pintype "passive"))
    )
    (net (code "94") (name "Net-(J6-Pad4)") (class "Default")
      (node (ref "J6") (pin "4") (pinfunction "4_4") (pintype "passive"))
      (node (ref "R116") (pin "2") (pinfunction "2_2") (pintype "passive"))
    )
    (net (code "95") (name "Net-(J6-Pad5)") (class "Default")
      (node (ref "J6") (pin "5") (pinfunction "5_5") (pintype "passive"))
      (node (ref "R117") (pin "2") (pinfunction "2_2") (pintype "passive"))
    )
    (net (code "96") (name "Net-(J11-Pad1)") (class "Default")
      (node (ref "J11") (pin "1") (pinfunction "1_1") (pintype "passive"))
      (node (ref "R113") (pin "2") (pinfunction "2_2") (pintype "passive"))
    )
    (net (code "97") (name "Net-(J11-Pad2)") (class "Default")
      (node (ref "J11") (pin "2") (pinfunction "2_2") (pintype "passive"))
      (node (ref "R114") (pin "2") (pinfunction "2_2") (pintype "passive"))
    )
    (net (code "98") (name "Net-(JP3-Pad1)") (class "Default")
      (node (ref "JP3") (pin "1") (pinfunction "1_1") (pintype "passive"))
      (node (ref "R108") (pin "2") (pinfunction "2_2") (pintype "passive"))
    )
    (net (code "99") (name "Net-(U12B-BOOT0)") (class "Default")
      (node (ref "R38") (pin "2") (pinfunction "2_2") (pintype "passive"))
      (node (ref "R46") (pin "1") (pinfunction "1_1") (pintype "passive"))
      (node (ref "U12") (pin "94") (pinfunction "BOOT0_94") (pintype "input"))
    )
    (net (code "100") (name "Net-(U12C-VCAP1)") (class "Default")
      (node (ref "C81") (pin "2") (pinfunction "2_2") (pintype "passive"))
      (node (ref "U12") (pin "48") (pinfunction "VCAP1_48") (pintype "power_in"))
    )
    (net (code "101") (name "Net-(U12C-VCAP2)") (class "Default")
      (node (ref "C82") (pin "2") (pinfunction "2_2") (pintype "passive"))
      (node (ref "U12") (pin "73") (pinfunction "VCAP2_73") (pintype "power_in"))
    )
    (net (code "102") (name "Net-(U12C-VDDA)") (class "Default")
      (node (ref "C75") (pin "2") (pinfunction "2_2") (pintype "passive"))
      (node (ref "C76") (pin "2") (pinfunction "2_2") (pintype "passive"))
      (node (ref "L7") (pin "2") (pinfunction "2_2") (pintype "passive"))
      (node (ref "U12") (pin "20") (pinfunction "VREF+_20") (pintype "power_in"))
      (node (ref "U12") (pin "21") (pinfunction "VDDA_21") (pintype "power_in"))
    )
    (net (code "103") (name "Net-(U21-DELAY{slash}MRST)") (class "Default")
      (node (ref "JP3") (pin "2") (pinfunction "2_2") (pintype "passive"))
      (node (ref "R109") (pin "2") (pinfunction "2_2") (pintype "passive"))
      (node (ref "U21") (pin "3") (pinfunction "DELAY/MRST_3") (pintype "passive"))
    )
    (net (code "104") (name "Net-(U21-DONE)") (class "Default")
      (node (ref "R107") (pin "1") (pinfunction "1_1") (pintype "passive"))
      (node (ref "U21") (pin "4") (pinfunction "DONE_4") (pintype "passive"))
    )
    (net (code "105") (name "Net-(U21-WAKE)") (class "Default")
      (node (ref "R106") (pin "1") (pinfunction "1_1") (pintype "passive"))
      (node (ref "U21") (pin "5") (pinfunction "WAKE_5") (pintype "passive"))
    )
    (net (code "106") (name "Net-(U21-~{RST})") (class "Default")
      (node (ref "R105") (pin "1") (pinfunction "1_1") (pintype "passive"))
      (node (ref "U21") (pin "6") (pinfunction "~{RST}_6") (pintype "passive"))
    )
    (net (code "107") (name "unconnected-(U12A-PB8-Pad95)") (class "Default")
      (node (ref "U12") (pin "95") (pinfunction "PB8_95") (pintype "bidirectional"))
    )
    (net (code "108") (name "unconnected-(U12A-PB9-Pad96)") (class "Default")
      (node (ref "U12") (pin "96") (pinfunction "PB9_96") (pintype "bidirectional"))
    )
    (net (code "109") (name "unconnected-(U12A-PC11-Pad79)") (class "Default")
      (node (ref "U12") (pin "79") (pinfunction "PC11_79") (pintype "bidirectional"))
    )
    (net (code "110") (name "unconnected-(U12B-PE5-Pad4)") (class "Default")
      (node (ref "U12") (pin "4") (pinfunction "PE5_4") (pintype "bidirectional"))
    )
  )
)
